# controller-board-ffc.net
KiCad netlist of a schematic drawn in EAGLE
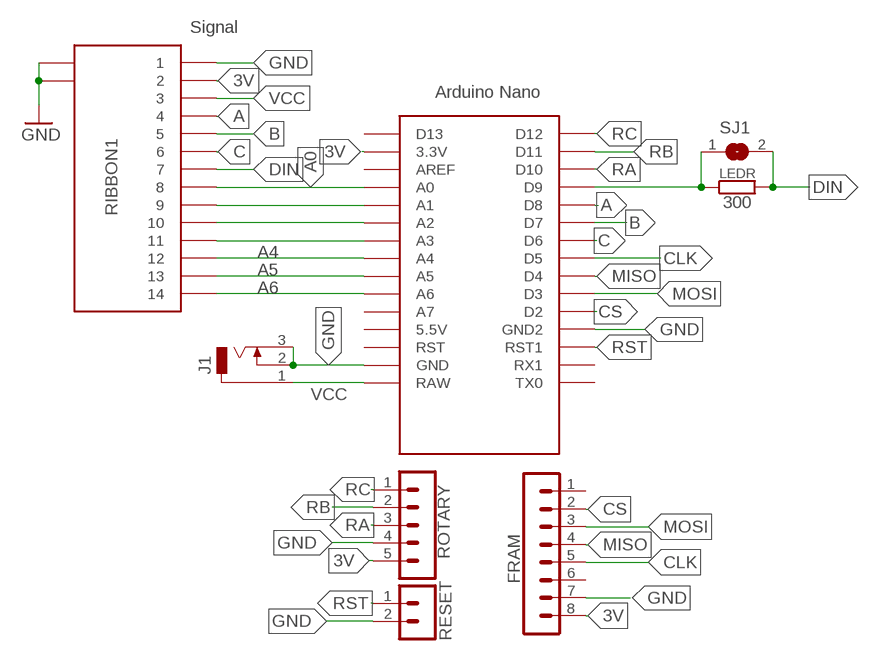
[diagram p0: schematic, sheet 1]

(export (version "E")
  (design (tool "Eeschema 10.0.6"))
  (components
    (comp (ref "FRAM")
      (value "MB85RS2MTA")
      (footprint "eagle-import:MA08-1")
      (libsource (lib "eagle-import") (part "MA08-1"))
    )
    (comp (ref "J1")
      (value "DCJ0202")
      (footprint "eagle-import:DCJ0202")
      (libsource (lib "eagle-import") (part "DCJ0202"))
    )
    (comp (ref "LEDR")
      (value "300")
      (footprint "eagle-import:0207_10")
      (libsource (lib "eagle-import") (part "R-EU_0207/10"))
    )
    (comp (ref "RESET")
      (value "B2B-PH-K")
      (footprint "eagle-import:B2B-PH-K")
      (libsource (lib "eagle-import") (part "B2B-PH-K"))
    )
    (comp (ref "RIBBON1")
      (value "Signal")
      (footprint "eagle-import:686114148922")
      (fields
        (field (name "MANUFACTURER_PART_NUMBER") "686114148922")
        (field (name "MOUSER_PART_NUMBER") "710-686114148922")
      )
      (libsource (lib "eagle-import") (part "686114148922"))
    )
    (comp (ref "ROTARY")
      (value "B5B-PH-K")
      (footprint "eagle-import:B5B-PH-K")
      (libsource (lib "eagle-import") (part "B5B-PH-K"))
    )
    (comp (ref "SJ1") (value "SJ") (footprint "eagle-import:SJ") (libsource (lib "eagle-import") (part "SJ")))
    (comp (ref "U$1")
      (value "NANO")
      (footprint "eagle-import:NANO")
      (libsource (lib "eagle-import") (part "NANO"))
    )
  )
  (nets
    (net (code "1") (name "/A4") (class "Default")
      (node (ref "RIBBON1") (pin "12") (pinfunction "12_12") (pintype "bidirectional"))
      (node (ref "U$1") (pin "A4") (pinfunction "A4_A4") (pintype "bidirectional"))
    )
    (net (code "2") (name "/A5") (class "Default")
      (node (ref "RIBBON1") (pin "13") (pinfunction "13_13") (pintype "bidirectional"))
      (node (ref "U$1") (pin "A5") (pinfunction "A5_A5") (pintype "bidirectional"))
    )
    (net (code "3") (name "/A6") (class "Default")
      (node (ref "RIBBON1") (pin "14") (pinfunction "14_14") (pintype "bidirectional"))
      (node (ref "U$1") (pin "A6") (pinfunction "A6_A6") (pintype "bidirectional"))
    )
    (net (code "4") (name "3V") (class "Default")
      (node (ref "FRAM") (pin "8") (pinfunction "8_8") (pintype "passive"))
      (node (ref "RIBBON1") (pin "2") (pinfunction "2_2") (pintype "bidirectional"))
      (node (ref "ROTARY") (pin "5") (pinfunction "5_5") (pintype "passive"))
      (node (ref "U$1") (pin "3.3V") (pinfunction "3.3V_3.3V") (pintype "bidirectional"))
    )
    (net (code "5") (name "A") (class "Default")
      (node (ref "RIBBON1") (pin "4") (pinfunction "4_4") (pintype "bidirectional"))
      (node (ref "U$1") (pin "D8") (pinfunction "D8_D8") (pintype "bidirectional"))
    )
    (net (code "6") (name "A0") (class "Default")
      (node (ref "RIBBON1") (pin "8") (pinfunction "8_8") (pintype "bidirectional"))
      (node (ref "U$1") (pin "A0") (pinfunction "A0_A0") (pintype "bidirectional"))
    )
    (net (code "7") (name "B") (class "Default")
      (node (ref "RIBBON1") (pin "5") (pinfunction "5_5") (pintype "bidirectional"))
      (node (ref "U$1") (pin "D7") (pinfunction "D7_D7") (pintype "bidirectional"))
    )
    (net (code "8") (name "C") (class "Default")
      (node (ref "RIBBON1") (pin "6") (pinfunction "6_6") (pintype "bidirectional"))
      (node (ref "U$1") (pin "D6") (pinfunction "D6_D6") (pintype "bidirectional"))
    )
    (net (code "9") (name "CLK") (class "Default")
      (node (ref "FRAM") (pin "5") (pinfunction "5_5") (pintype "passive"))
      (node (ref "U$1") (pin "D5") (pinfunction "D5_D5") (pintype "bidirectional"))
    )
    (net (code "10") (name "CS") (class "Default")
      (node (ref "FRAM") (pin "2") (pinfunction "2_2") (pintype "passive"))
      (node (ref "U$1") (pin "D2") (pinfunction "D2_D2") (pintype "bidirectional"))
    )
    (net (code "11") (name "DIN") (class "Default")
      (node (ref "LEDR") (pin "2") (pinfunction "2_2") (pintype "passive"))
      (node (ref "RIBBON1") (pin "7") (pinfunction "7_7") (pintype "bidirectional"))
      (node (ref "SJ1") (pin "2") (pinfunction "2_2") (pintype "passive"))
    )
    (net (code "12") (name "GND") (class "Default")
      (node (ref "FRAM") (pin "7") (pinfunction "7_7") (pintype "passive"))
      (node (ref "J1") (pin "2") (pinfunction "2_2") (pintype "passive"))
      (node (ref "J1") (pin "3") (pinfunction "3_3") (pintype "passive"))
      (node (ref "RESET") (pin "2") (pinfunction "2_2") (pintype "passive"))
      (node (ref "RIBBON1") (pin "1") (pinfunction "1_1") (pintype "bidirectional"))
      (node (ref "RIBBON1") (pin "MP1") (pinfunction "MP1_MP1") (pintype "bidirectional"))
      (node (ref "RIBBON1") (pin "MP2") (pinfunction "MP2_MP2") (pintype "bidirectional"))
      (node (ref "ROTARY") (pin "4") (pinfunction "4_4") (pintype "passive"))
      (node (ref "U$1") (pin "GND") (pinfunction "GND_GND") (pintype "bidirectional"))
      (node (ref "U$1") (pin "GND1") (pinfunction "GND2_GND1") (pintype "bidirectional"))
    )
    (net (code "13") (name "MISO") (class "Default")
      (node (ref "FRAM") (pin "4") (pinfunction "4_4") (pintype "passive"))
      (node (ref "U$1") (pin "D4") (pinfunction "D4_D4") (pintype "bidirectional"))
    )
    (net (code "14") (name "MOSI") (class "Default")
      (node (ref "FRAM") (pin "3") (pinfunction "3_3") (pintype "passive"))
      (node (ref "U$1") (pin "D3") (pinfunction "D3_D3") (pintype "bidirectional"))
    )
    (net (code "15") (name "Net-(LEDR-Pad1)") (class "Default")
      (node (ref "LEDR") (pin "1") (pinfunction "1_1") (pintype "passive"))
      (node (ref "SJ1") (pin "1") (pinfunction "1_1") (pintype "passive"))
      (node (ref "U$1") (pin "D9") (pinfunction "D9_D9") (pintype "bidirectional"))
    )
    (net (code "16") (name "Net-(RIBBON1-Pad9)") (class "Default")
      (node (ref "RIBBON1") (pin "9") (pinfunction "9_9") (pintype "bidirectional"))
      (node (ref "U$1") (pin "A1") (pinfunction "A1_A1") (pintype "bidirectional"))
    )
    (net (code "17") (name "Net-(RIBBON1-Pad10)") (class "Default")
      (node (ref "RIBBON1") (pin "10") (pinfunction "10_10") (pintype "bidirectional"))
      (node (ref "U$1") (pin "A2") (pinfunction "A2_A2") (pintype "bidirectional"))
    )
    (net (code "18") (name "Net-(RIBBON1-Pad11)") (class "Default")
      (node (ref "RIBBON1") (pin "11") (pinfunction "11_11") (pintype "bidirectional"))
      (node (ref "U$1") (pin "A3") (pinfunction "A3_A3") (pintype "bidirectional"))
    )
    (net (code "19") (name "RA") (class "Default")
      (node (ref "ROTARY") (pin "3") (pinfunction "3_3") (pintype "passive"))
      (node (ref "U$1") (pin "D10") (pinfunction "D10_D10") (pintype "bidirectional"))
    )
    (net (code "20") (name "RB") (class "Default")
      (node (ref "ROTARY") (pin "2") (pinfunction "2_2") (pintype "passive"))
      (node (ref "U$1") (pin "D11") (pinfunction "D11_D11") (pintype "bidirectional"))
    )
    (net (code "21") (name "RC") (class "Default")
      (node (ref "ROTARY") (pin "1") (pinfunction "1_1") (pintype "passive"))
      (node (ref "U$1") (pin "D12") (pinfunction "D12_D12") (pintype "bidirectional"))
    )
    (net (code "22") (name "RST") (class "Default")
      (node (ref "RESET") (pin "1") (pinfunction "1_1") (pintype "passive"))
      (node (ref "U$1") (pin "RST1") (pinfunction "RST1_RST1") (pintype "bidirectional"))
    )
    (net (code "23") (name "VCC") (class "Default")
      (node (ref "J1") (pin "1") (pinfunction "1_1") (pintype "passive"))
      (node (ref "RIBBON1") (pin "3") (pinfunction "3_3") (pintype "bidirectional"))
      (node (ref "U$1") (pin "RAW") (pinfunction "RAW_RAW") (pintype "bidirectional"))
    )
    (net (code "24") (name "unconnected-(FRAM-Pad1)") (class "Default")
      (node (ref "FRAM") (pin "1") (pinfunction "1_1") (pintype "passive"))
    )
    (net (code "25") (name "unconnected-(FRAM-Pad6)") (class "Default")
      (node (ref "FRAM") (pin "6") (pinfunction "6_6") (pintype "passive"))
    )
    (net (code "26") (name "unconnected-(U$1-5.5V-Pad5V)") (class "Default")
      (node (ref "U$1") (pin "5V") (pinfunction "5.5V_5V") (pintype "bidirectional"))
    )
    (net (code "27") (name "unconnected-(U$1-PadA7)") (class "Default")
      (node (ref "U$1") (pin "A7") (pinfunction "A7_A7") (pintype "bidirectional"))
    )
    (net (code "28") (name "unconnected-(U$1-PadAREF)") (class "Default")
      (node (ref "U$1") (pin "AREF") (pinfunction "AREF_AREF") (pintype "bidirectional"))
    )
    (net (code "29") (name "unconnected-(U$1-PadD13)") (class "Default")
      (node (ref "U$1") (pin "D13") (pinfunction "D13_D13") (pintype "bidirectional"))
    )
    (net (code "30") (name "unconnected-(U$1-PadICSP1)") (class "Default")
      (node (ref "U$1") (pin "ICSP1") (pinfunction "ICSP1_ICSP1") (pintype "bidirectional"))
    )
    (net (code "31") (name "unconnected-(U$1-PadICSP2)") (class "Default")
      (node (ref "U$1") (pin "ICSP2") (pinfunction "ICSP2_ICSP2") (pintype "bidirectional"))
    )
    (net (code "32") (name "unconnected-(U$1-PadICSP3)") (class "Default")
      (node (ref "U$1") (pin "ICSP3") (pinfunction "ICSP3_ICSP3") (pintype "bidirectional"))
    )
    (net (code "33") (name "unconnected-(U$1-PadICSP4)") (class "Default")
      (node (ref "U$1") (pin "ICSP4") (pinfunction "ICSP4_ICSP4") (pintype "bidirectional"))
    )
    (net (code "34") (name "unconnected-(U$1-PadICSP5)") (class "Default")
      (node (ref "U$1") (pin "ICSP5") (pinfunction "ICSP5_ICSP5") (pintype "bidirectional"))
    )
    (net (code "35") (name "unconnected-(U$1-PadICSP6)") (class "Default")
      (node (ref "U$1") (pin "ICSP6") (pinfunction "ICSP6_ICSP6") (pintype "bidirectional"))
    )
    (net (code "36") (name "unconnected-(U$1-PadRST)") (class "Default")
      (node (ref "U$1") (pin "RST") (pinfunction "RST_RST") (pintype "bidirectional"))
    )
    (net (code "37") (name "unconnected-(U$1-PadRX1)") (class "Default")
      (node (ref "U$1") (pin "RX1") (pinfunction "RX1_RX1") (pintype "bidirectional"))
    )
    (net (code "38") (name "unconnected-(U$1-PadTX0)") (class "Default")
      (node (ref "U$1") (pin "TX0") (pinfunction "TX0_TX0") (pintype "bidirectional"))
    )
  )
)
